# CPU_V1_1.net
KiCad netlist of a schematic drawn in EAGLE
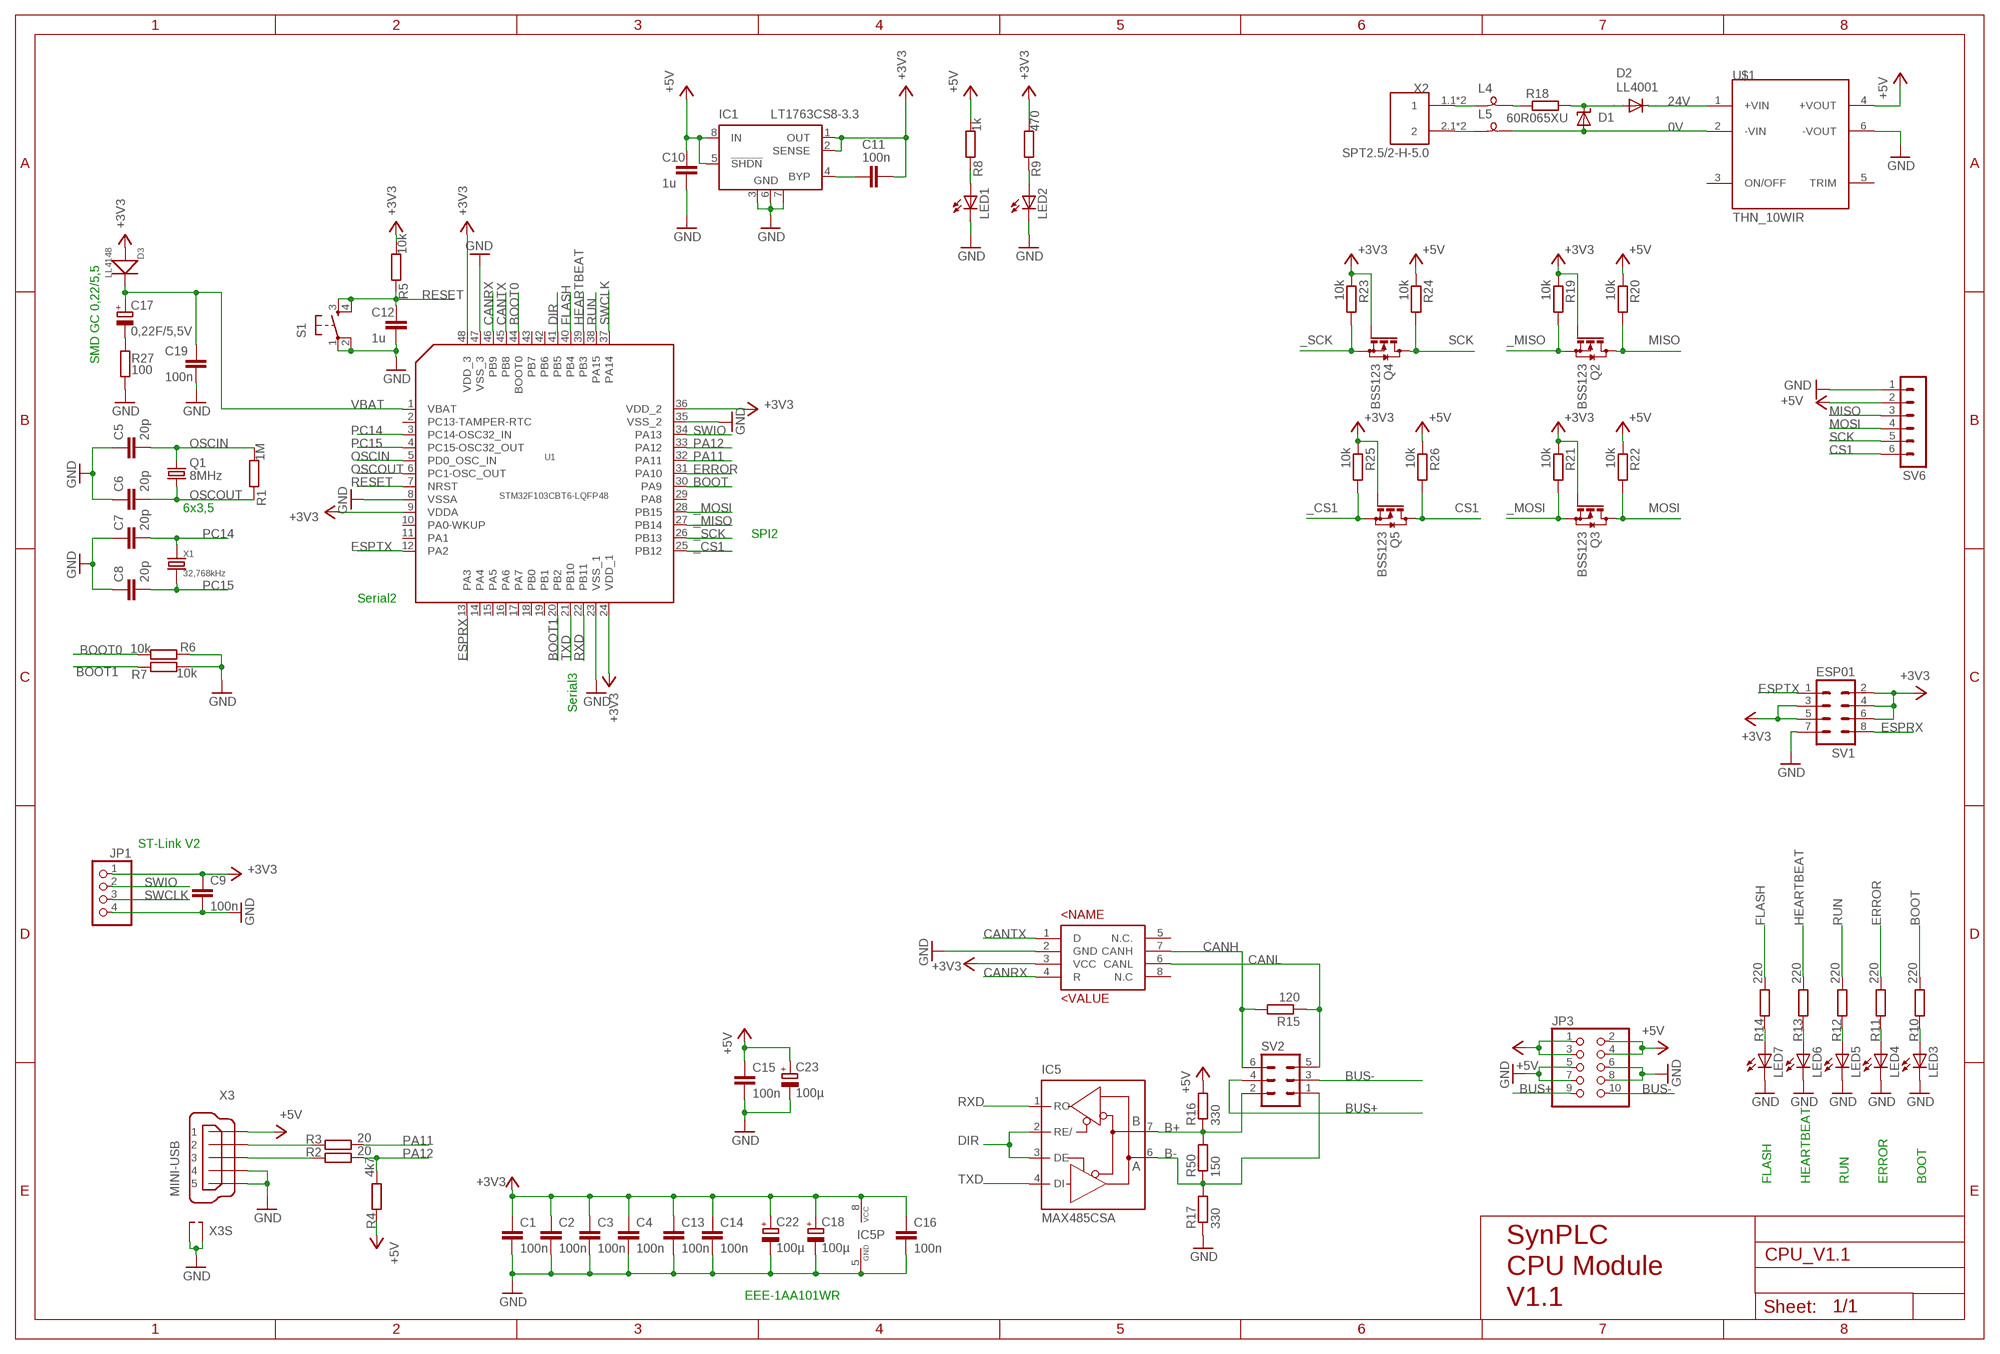
[diagram p0: schematic, sheet 1]

(export (version "E")
  (design (tool "Eeschema 10.0.6"))
  (components
    (comp (ref "C1")
      (value "100n")
      (footprint "eagle-import:C0805K")
      (libsource (lib "eagle-import") (part "C-EUC0805K"))
    )
    (comp (ref "C2")
      (value "100n")
      (footprint "eagle-import:C0805K")
      (libsource (lib "eagle-import") (part "C-EUC0805K"))
    )
    (comp (ref "C3")
      (value "100n")
      (footprint "eagle-import:C0805K")
      (libsource (lib "eagle-import") (part "C-EUC0805K"))
    )
    (comp (ref "C4")
      (value "100n")
      (footprint "eagle-import:C0805K")
      (libsource (lib "eagle-import") (part "C-EUC0805K"))
    )
    (comp (ref "C5")
      (value "20p")
      (footprint "eagle-import:C0805K")
      (libsource (lib "eagle-import") (part "C-EUC0805K"))
    )
    (comp (ref "C6")
      (value "20p")
      (footprint "eagle-import:C0805K")
      (libsource (lib "eagle-import") (part "C-EUC0805K"))
    )
    (comp (ref "C7")
      (value "20p")
      (footprint "eagle-import:C0805K")
      (libsource (lib "eagle-import") (part "C-EUC0805K"))
    )
    (comp (ref "C8")
      (value "20p")
      (footprint "eagle-import:C0805K")
      (libsource (lib "eagle-import") (part "C-EUC0805K"))
    )
    (comp (ref "C9")
      (value "100n")
      (footprint "eagle-import:C0805K")
      (libsource (lib "eagle-import") (part "C-EUC0805K"))
    )
    (comp (ref "C10")
      (value "1u")
      (footprint "eagle-import:C0805K")
      (libsource (lib "eagle-import") (part "C-EUC0805K"))
    )
    (comp (ref "C11")
      (value "100n")
      (footprint "eagle-import:C0805K")
      (libsource (lib "eagle-import") (part "C-EUC0805K"))
    )
    (comp (ref "C12")
      (value "1u")
      (footprint "eagle-import:C0805K")
      (libsource (lib "eagle-import") (part "C-EUC0805K"))
    )
    (comp (ref "C13")
      (value "100n")
      (footprint "eagle-import:C0805K")
      (libsource (lib "eagle-import") (part "C-EUC0805K"))
    )
    (comp (ref "C14")
      (value "100n")
      (footprint "eagle-import:C0805K")
      (libsource (lib "eagle-import") (part "C-EUC0805K"))
    )
    (comp (ref "C15")
      (value "100n")
      (footprint "eagle-import:C0805")
      (libsource (lib "eagle-import") (part "C-EUC0805"))
    )
    (comp (ref "C16")
      (value "100n")
      (footprint "eagle-import:C0805")
      (libsource (lib "eagle-import") (part "C-EUC0805"))
    )
    (comp (ref "C17")
      (value "0,22F/5,5V")
      (footprint "eagle-import:PANASONIC_G")
      (libsource (lib "eagle-import") (part "CPOL-EUG"))
    )
    (comp (ref "C18")
      (value "100µ")
      (footprint "eagle-import:153CLV-0505")
      (libsource (lib "eagle-import") (part "CPOL-EU153CLV-0505"))
    )
    (comp (ref "C19")
      (value "100n")
      (footprint "eagle-import:C0805K")
      (libsource (lib "eagle-import") (part "C-EUC0805K"))
    )
    (comp (ref "C22")
      (value "100µ")
      (footprint "eagle-import:153CLV-0505")
      (libsource (lib "eagle-import") (part "CPOL-EU153CLV-0505"))
    )
    (comp (ref "C23")
      (value "100µ")
      (footprint "eagle-import:153CLV-0505")
      (libsource (lib "eagle-import") (part "CPOL-EU153CLV-0505"))
    )
    (comp (ref "D1")
      (value "SUPPRESSOR-SMBJ")
      (footprint "eagle-import:SMBJ")
      (libsource (lib "eagle-import") (part "SUPPRESSOR-SMBJ"))
    )
    (comp (ref "D2")
      (value "LL4001")
      (footprint "eagle-import:SOD-123_MINI-SMA")
      (libsource (lib "eagle-import") (part "CGRM400-G1"))
    )
    (comp (ref "D3")
      (value "LL4148")
      (footprint "eagle-import:LL-34")
      (libsource (lib "eagle-import") (part "DIODE'1N4148-SMD'"))
    )
    (comp (ref "IC1")
      (value "LT1763CS8-3.3")
      (footprint "eagle-import:SOIC8")
      (libsource (lib "eagle-import") (part "LT1763CS8-3.3"))
    )
    (comp (ref "IC5")
      (value "MAX485CSA")
      (footprint "eagle-import:SO08")
      (fields (field (name "MF") "MAXIM") (field (name "MPN") "MAX481CSA"))
      (libsource (lib "eagle-import") (part "MAX481CSA"))
    )
    (comp (ref "JP1")
      (value "PINHD-1X4/90")
      (footprint "eagle-import:1X04_90")
      (libsource (lib "eagle-import") (part "PINHD-1X4/90"))
    )
    (comp (ref "JP3")
      (value "PINHD-2X5/90")
      (footprint "eagle-import:2X05_90")
      (libsource (lib "eagle-import") (part "PINHD-2X5/90"))
    )
    (comp (ref "L4")
      (value "SM-B5")
      (footprint "eagle-import:SM-B5")
      (libsource (lib "eagle-import") (part "SM-B5"))
    )
    (comp (ref "L5")
      (value "SM-B5")
      (footprint "eagle-import:SM-B5")
      (libsource (lib "eagle-import") (part "SM-B5"))
    )
    (comp (ref "LED1")
      (value "LEDSML0805")
      (footprint "eagle-import:SML0805")
      (libsource (lib "eagle-import") (part "LEDSML0805"))
    )
    (comp (ref "LED2")
      (value "LEDSML0805")
      (footprint "eagle-import:SML0805")
      (libsource (lib "eagle-import") (part "LEDSML0805"))
    )
    (comp (ref "LED3")
      (value "LED3MM")
      (footprint "eagle-import:LED3MM")
      (libsource (lib "eagle-import") (part "LED3MM"))
    )
    (comp (ref "LED4")
      (value "LED3MM")
      (footprint "eagle-import:LED3MM")
      (libsource (lib "eagle-import") (part "LED3MM"))
    )
    (comp (ref "LED5")
      (value "LED3MM")
      (footprint "eagle-import:LED3MM")
      (libsource (lib "eagle-import") (part "LED3MM"))
    )
    (comp (ref "LED6")
      (value "LED3MM")
      (footprint "eagle-import:LED3MM")
      (libsource (lib "eagle-import") (part "LED3MM"))
    )
    (comp (ref "LED7")
      (value "LED3MM")
      (footprint "eagle-import:LED3MM")
      (libsource (lib "eagle-import") (part "LED3MM"))
    )
    (comp (ref "Q1")
      (value "8MHz")
      (footprint "eagle-import:11.4X4.5")
      (libsource (lib "eagle-import") (part "KX-K"))
    )
    (comp (ref "Q2")
      (value "BSS123")
      (footprint "eagle-import:SOT23")
      (libsource (lib "eagle-import") (part "BSS123"))
    )
    (comp (ref "Q3")
      (value "BSS123")
      (footprint "eagle-import:SOT23")
      (libsource (lib "eagle-import") (part "BSS123"))
    )
    (comp (ref "Q4")
      (value "BSS123")
      (footprint "eagle-import:SOT23")
      (libsource (lib "eagle-import") (part "BSS123"))
    )
    (comp (ref "Q5")
      (value "BSS123")
      (footprint "eagle-import:SOT23")
      (libsource (lib "eagle-import") (part "BSS123"))
    )
    (comp (ref "R1")
      (value "1M")
      (footprint "eagle-import:R0805")
      (libsource (lib "eagle-import") (part "R-EU_R0805"))
    )
    (comp (ref "R2")
      (value "20")
      (footprint "eagle-import:R0805")
      (libsource (lib "eagle-import") (part "R-EU_R0805"))
    )
    (comp (ref "R3")
      (value "20")
      (footprint "eagle-import:R0805")
      (libsource (lib "eagle-import") (part "R-EU_R0805"))
    )
    (comp (ref "R4")
      (value "4k7")
      (footprint "eagle-import:R0805")
      (libsource (lib "eagle-import") (part "R-EU_R0805"))
    )
    (comp (ref "R5")
      (value "10k")
      (footprint "eagle-import:R0805")
      (libsource (lib "eagle-import") (part "R-EU_R0805"))
    )
    (comp (ref "R6")
      (value "10k")
      (footprint "eagle-import:R0805")
      (libsource (lib "eagle-import") (part "R-EU_R0805"))
    )
    (comp (ref "R7")
      (value "10k")
      (footprint "eagle-import:R0805")
      (libsource (lib "eagle-import") (part "R-EU_R0805"))
    )
    (comp (ref "R8")
      (value "1k")
      (footprint "eagle-import:R0805")
      (libsource (lib "eagle-import") (part "R-EU_R0805"))
    )
    (comp (ref "R9")
      (value "470")
      (footprint "eagle-import:R0805")
      (libsource (lib "eagle-import") (part "R-EU_R0805"))
    )
    (comp (ref "R10")
      (value "220")
      (footprint "eagle-import:R0805")
      (libsource (lib "eagle-import") (part "R-EU_R0805"))
    )
    (comp (ref "R11")
      (value "220")
      (footprint "eagle-import:R0805")
      (libsource (lib "eagle-import") (part "R-EU_R0805"))
    )
    (comp (ref "R12")
      (value "220")
      (footprint "eagle-import:R0805")
      (libsource (lib "eagle-import") (part "R-EU_R0805"))
    )
    (comp (ref "R13")
      (value "220")
      (footprint "eagle-import:R0805")
      (libsource (lib "eagle-import") (part "R-EU_R0805"))
    )
    (comp (ref "R14")
      (value "220")
      (footprint "eagle-import:R0805")
      (libsource (lib "eagle-import") (part "R-EU_R0805"))
    )
    (comp (ref "R15")
      (value "120")
      (footprint "eagle-import:R0805")
      (libsource (lib "eagle-import") (part "R-EU_R0805"))
    )
    (comp (ref "R16")
      (value "330")
      (footprint "eagle-import:R0805")
      (libsource (lib "eagle-import") (part "R-EU_R0805"))
    )
    (comp (ref "R17")
      (value "330")
      (footprint "eagle-import:R0805")
      (libsource (lib "eagle-import") (part "R-EU_R0805"))
    )
    (comp (ref "R18")
      (value "60R065XU")
      (footprint "eagle-import:0204_5")
      (libsource (lib "eagle-import") (part "R-EU_0204/5"))
    )
    (comp (ref "R19")
      (value "10k")
      (footprint "eagle-import:R0805")
      (libsource (lib "eagle-import") (part "R-EU_R0805"))
    )
    (comp (ref "R20")
      (value "10k")
      (footprint "eagle-import:R0805")
      (libsource (lib "eagle-import") (part "R-EU_R0805"))
    )
    (comp (ref "R21")
      (value "10k")
      (footprint "eagle-import:R0805")
      (libsource (lib "eagle-import") (part "R-EU_R0805"))
    )
    (comp (ref "R22")
      (value "10k")
      (footprint "eagle-import:R0805")
      (libsource (lib "eagle-import") (part "R-EU_R0805"))
    )
    (comp (ref "R23")
      (value "10k")
      (footprint "eagle-import:R0805")
      (libsource (lib "eagle-import") (part "R-EU_R0805"))
    )
    (comp (ref "R24")
      (value "10k")
      (footprint "eagle-import:R0805")
      (libsource (lib "eagle-import") (part "R-EU_R0805"))
    )
    (comp (ref "R25")
      (value "10k")
      (footprint "eagle-import:R0805")
      (libsource (lib "eagle-import") (part "R-EU_R0805"))
    )
    (comp (ref "R26")
      (value "10k")
      (footprint "eagle-import:R0805")
      (libsource (lib "eagle-import") (part "R-EU_R0805"))
    )
    (comp (ref "R27")
      (value "100")
      (footprint "eagle-import:R0805")
      (libsource (lib "eagle-import") (part "R-EU_R0805"))
    )
    (comp (ref "R50")
      (value "150")
      (footprint "eagle-import:R0805")
      (libsource (lib "eagle-import") (part "R-EU_R0805"))
    )
    (comp (ref "S1")
      (value "TAC_SWITCHPTH")
      (footprint "eagle-import:TACTILE-PTH")
      (libsource (lib "eagle-import") (part "TAC_SWITCHPTH"))
    )
    (comp (ref "SV1")
      (value "ESP01")
      (footprint "eagle-import:MA04-2")
      (libsource (lib "eagle-import") (part "MA04-2"))
    )
    (comp (ref "SV2")
      (value "MA03-2")
      (footprint "eagle-import:MA03-2")
      (libsource (lib "eagle-import") (part "MA03-2"))
    )
    (comp (ref "SV6")
      (value "MA06-1")
      (footprint "eagle-import:MA06-1")
      (libsource (lib "eagle-import") (part "MA06-1"))
    )
    (comp (ref "U$1")
      (value "THN_10WIR")
      (footprint "eagle-import:THN10WIR")
      (libsource (lib "eagle-import") (part "THN_10WIR"))
    )
    (comp (ref "U$3")
      (value "SN65HVD232")
      (footprint "eagle-import:SO-08")
      (libsource (lib "eagle-import") (part "SN65HVD232"))
    )
    (comp (ref "U1")
      (value "STM32F103CBT6-LQFP48")
      (footprint "eagle-import:LQFP48-0.5-7X7MM")
      (fields (field (name "MPN") "STM32F103CBT6"))
      (libsource (lib "eagle-import") (part "MCU-STM32F103CBT6(LQFP48)"))
    )
    (comp (ref "X1")
      (value "32,768kHz")
      (footprint "eagle-import:X2-2.0-D9.1XL3.3MM")
      (libsource (lib "eagle-import") (part "CRYSTAL'9133'"))
    )
    (comp (ref "X2")
      (value "SPT2.5/2-H-5.0")
      (footprint "eagle-import:SPT2")
      (libsource (lib "eagle-import") (part "SPT2.5/2-H-5.0"))
    )
    (comp (ref "X3")
      (value "MINI-USB")
      (footprint "eagle-import:32005-601")
      (libsource (lib "eagle-import") (part "MINI-USB_SHIELD5P2-32005-601"))
    )
  )
  (nets
    (net (code "1") (name "+3V3") (class "Default")
      (node (ref "C1") (pin "1") (pinfunction "1_1") (pintype "passive"))
      (node (ref "C11") (pin "1") (pinfunction "1_1") (pintype "passive"))
      (node (ref "C13") (pin "1") (pinfunction "1_1") (pintype "passive"))
      (node (ref "C14") (pin "1") (pinfunction "1_1") (pintype "passive"))
      (node (ref "C16") (pin "1") (pinfunction "1_1") (pintype "passive"))
      (node (ref "C18") (pin "+") (pinfunction "+_+") (pintype "passive"))
      (node (ref "C2") (pin "1") (pinfunction "1_1") (pintype "passive"))
      (node (ref "C22") (pin "+") (pinfunction "+_+") (pintype "passive"))
      (node (ref "C3") (pin "1") (pinfunction "1_1") (pintype "passive"))
      (node (ref "C4") (pin "1") (pinfunction "1_1") (pintype "passive"))
      (node (ref "C9") (pin "1") (pinfunction "1_1") (pintype "passive"))
      (node (ref "D3") (pin "A") (pinfunction "+_A") (pintype "passive"))
      (node (ref "IC1") (pin "1") (pinfunction "OUT_1") (pintype "passive"))
      (node (ref "IC1") (pin "2") (pinfunction "SENSE_2") (pintype "input"))
      (node (ref "IC5") (pin "8") (pinfunction "VCC_8") (pintype "power_in"))
      (node (ref "JP1") (pin "1") (pinfunction "1_1") (pintype "passive"))
      (node (ref "Q2") (pin "1") (pinfunction "G_1") (pintype "passive"))
      (node (ref "Q3") (pin "1") (pinfunction "G_1") (pintype "passive"))
      (node (ref "Q4") (pin "1") (pinfunction "G_1") (pintype "passive"))
      (node (ref "Q5") (pin "1") (pinfunction "G_1") (pintype "passive"))
      (node (ref "R19") (pin "1") (pinfunction "1_1") (pintype "passive"))
      (node (ref "R21") (pin "1") (pinfunction "1_1") (pintype "passive"))
      (node (ref "R23") (pin "1") (pinfunction "1_1") (pintype "passive"))
      (node (ref "R25") (pin "1") (pinfunction "1_1") (pintype "passive"))
      (node (ref "R5") (pin "2") (pinfunction "2_2") (pintype "passive"))
      (node (ref "R9") (pin "2") (pinfunction "2_2") (pintype "passive"))
      (node (ref "SV1") (pin "2") (pinfunction "2_2") (pintype "passive"))
      (node (ref "SV1") (pin "3") (pinfunction "3_3") (pintype "passive"))
      (node (ref "SV1") (pin "4") (pinfunction "4_4") (pintype "passive"))
      (node (ref "SV1") (pin "5") (pinfunction "5_5") (pintype "passive"))
      (node (ref "SV1") (pin "6") (pinfunction "6_6") (pintype "passive"))
      (node (ref "U$3") (pin "3") (pinfunction "VCC_3") (pintype "bidirectional"))
      (node (ref "U1") (pin "24") (pinfunction "VDD_1_24") (pintype "bidirectional"))
      (node (ref "U1") (pin "36") (pinfunction "VDD_2_36") (pintype "bidirectional"))
      (node (ref "U1") (pin "48") (pinfunction "VDD_3_48") (pintype "bidirectional"))
      (node (ref "U1") (pin "9") (pinfunction "VDDA_9") (pintype "bidirectional"))
    )
    (net (code "2") (name "+5V") (class "Default")
      (node (ref "C10") (pin "1") (pinfunction "1_1") (pintype "passive"))
      (node (ref "C15") (pin "1") (pinfunction "1_1") (pintype "passive"))
      (node (ref "C23") (pin "+") (pinfunction "+_+") (pintype "passive"))
      (node (ref "IC1") (pin "5") (pinfunction "~{SHDN}_5") (pintype "input"))
      (node (ref "IC1") (pin "8") (pinfunction "IN_8") (pintype "input"))
      (node (ref "JP3") (pin "1") (pinfunction "1_1") (pintype "passive"))
      (node (ref "JP3") (pin "2") (pinfunction "2_2") (pintype "passive"))
      (node (ref "JP3") (pin "3") (pinfunction "3_3") (pintype "passive"))
      (node (ref "JP3") (pin "4") (pinfunction "4_4") (pintype "passive"))
      (node (ref "R16") (pin "2") (pinfunction "2_2") (pintype "passive"))
      (node (ref "R20") (pin "1") (pinfunction "1_1") (pintype "passive"))
      (node (ref "R22") (pin "1") (pinfunction "1_1") (pintype "passive"))
      (node (ref "R24") (pin "1") (pinfunction "1_1") (pintype "passive"))
      (node (ref "R26") (pin "1") (pinfunction "1_1") (pintype "passive"))
      (node (ref "R4") (pin "1") (pinfunction "1_1") (pintype "passive"))
      (node (ref "R8") (pin "2") (pinfunction "2_2") (pintype "passive"))
      (node (ref "SV6") (pin "2") (pinfunction "2_2") (pintype "passive"))
      (node (ref "U$1") (pin "4") (pinfunction "+VOUT_4") (pintype "bidirectional"))
      (node (ref "X3") (pin "1") (pinfunction "1_1") (pintype "passive"))
    )
    (net (code "3") (name "/0V") (class "Default")
      (node (ref "D1") (pin "A") (pinfunction "A_A") (pintype "passive"))
      (node (ref "L5") (pin "1") (pinfunction "1_1") (pintype "passive"))
      (node (ref "U$1") (pin "2") (pinfunction "-VIN_2") (pintype "bidirectional"))
    )
    (net (code "4") (name "/24V") (class "Default")
      (node (ref "D2") (pin "C") (pinfunction "C_C") (pintype "passive"))
      (node (ref "U$1") (pin "1") (pinfunction "+VIN_1") (pintype "bidirectional"))
    )
    (net (code "5") (name "/B+") (class "Default")
      (node (ref "IC5") (pin "7") (pinfunction "B_7") (pintype "passive"))
      (node (ref "R16") (pin "1") (pinfunction "1_1") (pintype "passive"))
      (node (ref "R50") (pin "2") (pinfunction "2_2") (pintype "passive"))
      (node (ref "SV2") (pin "2") (pinfunction "2_2") (pintype "passive"))
    )
    (net (code "6") (name "/B-") (class "Default")
      (node (ref "IC5") (pin "6") (pinfunction "A_6") (pintype "passive"))
      (node (ref "R17") (pin "2") (pinfunction "2_2") (pintype "passive"))
      (node (ref "R50") (pin "1") (pinfunction "1_1") (pintype "passive"))
      (node (ref "SV2") (pin "1") (pinfunction "1_1") (pintype "passive"))
    )
    (net (code "7") (name "/BOOT") (class "Default")
      (node (ref "R10") (pin "2") (pinfunction "2_2") (pintype "passive"))
      (node (ref "U1") (pin "30") (pinfunction "PA9_30") (pintype "bidirectional"))
    )
    (net (code "8") (name "/BOOT0") (class "Default")
      (node (ref "R6") (pin "2") (pinfunction "2_2") (pintype "passive"))
      (node (ref "U1") (pin "44") (pinfunction "BOOT0_44") (pintype "bidirectional"))
    )
    (net (code "9") (name "/BOOT1") (class "Default")
      (node (ref "R7") (pin "1") (pinfunction "1_1") (pintype "passive"))
      (node (ref "U1") (pin "20") (pinfunction "PB2_20") (pintype "bidirectional"))
    )
    (net (code "10") (name "/BUS+") (class "Default")
      (node (ref "JP3") (pin "9") (pinfunction "9_9") (pintype "passive"))
      (node (ref "SV2") (pin "4") (pinfunction "4_4") (pintype "passive"))
    )
    (net (code "11") (name "/BUS-") (class "Default")
      (node (ref "JP3") (pin "10") (pinfunction "10_10") (pintype "passive"))
      (node (ref "SV2") (pin "3") (pinfunction "3_3") (pintype "passive"))
    )
    (net (code "12") (name "/CANH") (class "Default")
      (node (ref "R15") (pin "2") (pinfunction "2_2") (pintype "passive"))
      (node (ref "SV2") (pin "6") (pinfunction "6_6") (pintype "passive"))
      (node (ref "U$3") (pin "7") (pinfunction "CANH_7") (pintype "bidirectional"))
    )
    (net (code "13") (name "/CANL") (class "Default")
      (node (ref "R15") (pin "1") (pinfunction "1_1") (pintype "passive"))
      (node (ref "SV2") (pin "5") (pinfunction "5_5") (pintype "passive"))
      (node (ref "U$3") (pin "6") (pinfunction "CANL_6") (pintype "bidirectional"))
    )
    (net (code "14") (name "/CANRX") (class "Default")
      (node (ref "U$3") (pin "4") (pinfunction "R_4") (pintype "bidirectional"))
      (node (ref "U1") (pin "46") (pinfunction "PB9_46") (pintype "bidirectional"))
    )
    (net (code "15") (name "/CANTX") (class "Default")
      (node (ref "U$3") (pin "1") (pinfunction "D_1") (pintype "bidirectional"))
      (node (ref "U1") (pin "45") (pinfunction "PB8_45") (pintype "bidirectional"))
    )
    (net (code "16") (name "/CS1") (class "Default")
      (node (ref "Q5") (pin "3") (pinfunction "D_3") (pintype "passive"))
      (node (ref "R26") (pin "2") (pinfunction "2_2") (pintype "passive"))
      (node (ref "SV6") (pin "6") (pinfunction "6_6") (pintype "passive"))
    )
    (net (code "17") (name "/DIR") (class "Default")
      (node (ref "IC5") (pin "2") (pinfunction "RE/_2") (pintype "input"))
      (node (ref "IC5") (pin "3") (pinfunction "DE_3") (pintype "input"))
      (node (ref "U1") (pin "41") (pinfunction "PB5_41") (pintype "bidirectional"))
    )
    (net (code "18") (name "/ERROR") (class "Default")
      (node (ref "R11") (pin "2") (pinfunction "2_2") (pintype "passive"))
      (node (ref "U1") (pin "31") (pinfunction "PA10_31") (pintype "bidirectional"))
    )
    (net (code "19") (name "/ESPRX") (class "Default")
      (node (ref "SV1") (pin "8") (pinfunction "8_8") (pintype "passive"))
      (node (ref "U1") (pin "13") (pinfunction "PA3_13") (pintype "bidirectional"))
    )
    (net (code "20") (name "/ESPTX") (class "Default")
      (node (ref "SV1") (pin "1") (pinfunction "1_1") (pintype "passive"))
      (node (ref "U1") (pin "12") (pinfunction "PA2_12") (pintype "bidirectional"))
    )
    (net (code "21") (name "/FLASH") (class "Default")
      (node (ref "R14") (pin "2") (pinfunction "2_2") (pintype "passive"))
      (node (ref "U1") (pin "40") (pinfunction "PB4_40") (pintype "bidirectional"))
    )
    (net (code "22") (name "/HEARTBEAT") (class "Default")
      (node (ref "R13") (pin "2") (pinfunction "2_2") (pintype "passive"))
      (node (ref "U1") (pin "39") (pinfunction "PB3_39") (pintype "bidirectional"))
    )
    (net (code "23") (name "/MISO") (class "Default")
      (node (ref "Q2") (pin "3") (pinfunction "D_3") (pintype "passive"))
      (node (ref "R20") (pin "2") (pinfunction "2_2") (pintype "passive"))
      (node (ref "SV6") (pin "3") (pinfunction "3_3") (pintype "passive"))
    )
    (net (code "24") (name "/MOSI") (class "Default")
      (node (ref "Q3") (pin "3") (pinfunction "D_3") (pintype "passive"))
      (node (ref "R22") (pin "2") (pinfunction "2_2") (pintype "passive"))
      (node (ref "SV6") (pin "4") (pinfunction "4_4") (pintype "passive"))
    )
    (net (code "25") (name "/OSCIN") (class "Default")
      (node (ref "C5") (pin "2") (pinfunction "2_2") (pintype "passive"))
      (node (ref "Q1") (pin "2") (pinfunction "2_2") (pintype "passive"))
      (node (ref "R1") (pin "2") (pinfunction "2_2") (pintype "passive"))
      (node (ref "U1") (pin "5") (pinfunction "PD0_OSC_IN_5") (pintype "bidirectional"))
    )
    (net (code "26") (name "/OSCOUT") (class "Default")
      (node (ref "C6") (pin "2") (pinfunction "2_2") (pintype "passive"))
      (node (ref "Q1") (pin "1") (pinfunction "1_1") (pintype "passive"))
      (node (ref "R1") (pin "1") (pinfunction "1_1") (pintype "passive"))
      (node (ref "U1") (pin "6") (pinfunction "PC1-OSC_OUT_6") (pintype "bidirectional"))
    )
    (net (code "27") (name "/PA11") (class "Default")
      (node (ref "R3") (pin "2") (pinfunction "2_2") (pintype "passive"))
      (node (ref "U1") (pin "32") (pinfunction "PA11_32") (pintype "bidirectional"))
    )
    (net (code "28") (name "/PA12") (class "Default")
      (node (ref "R2") (pin "2") (pinfunction "2_2") (pintype "passive"))
      (node (ref "R4") (pin "2") (pinfunction "2_2") (pintype "passive"))
      (node (ref "U1") (pin "33") (pinfunction "PA12_33") (pintype "bidirectional"))
    )
    (net (code "29") (name "/PC14") (class "Default")
      (node (ref "C7") (pin "2") (pinfunction "2_2") (pintype "passive"))
      (node (ref "U1") (pin "3") (pinfunction "PC14-OSC32_IN_3") (pintype "bidirectional"))
      (node (ref "X1") (pin "2") (pinfunction "2_2") (pintype "passive"))
    )
    (net (code "30") (name "/PC15") (class "Default")
      (node (ref "C8") (pin "2") (pinfunction "2_2") (pintype "passive"))
      (node (ref "U1") (pin "4") (pinfunction "PC15-OSC32_OUT_4") (pintype "bidirectional"))
      (node (ref "X1") (pin "1") (pinfunction "1_1") (pintype "passive"))
    )
    (net (code "31") (name "/RESET") (class "Default")
      (node (ref "C12") (pin "1") (pinfunction "1_1") (pintype "passive"))
      (node (ref "R5") (pin "1") (pinfunction "1_1") (pintype "passive"))
      (node (ref "S1") (pin "3") (pinfunction "3_3") (pintype "passive"))
      (node (ref "S1") (pin "4") (pinfunction "4_4") (pintype "passive"))
      (node (ref "U1") (pin "7") (pinfunction "NRST_7") (pintype "bidirectional"))
    )
    (net (code "32") (name "/RUN") (class "Default")
      (node (ref "R12") (pin "2") (pinfunction "2_2") (pintype "passive"))
      (node (ref "U1") (pin "38") (pinfunction "PA15_38") (pintype "bidirectional"))
    )
    (net (code "33") (name "/RXD") (class "Default")
      (node (ref "IC5") (pin "1") (pinfunction "RO_1") (pintype "output"))
      (node (ref "U1") (pin "22") (pinfunction "PB11_22") (pintype "bidirectional"))
    )
    (net (code "34") (name "/SCK") (class "Default")
      (node (ref "Q4") (pin "3") (pinfunction "D_3") (pintype "passive"))
      (node (ref "R24") (pin "2") (pinfunction "2_2") (pintype "passive"))
      (node (ref "SV6") (pin "5") (pinfunction "5_5") (pintype "passive"))
    )
    (net (code "35") (name "/SWCLK") (class "Default")
      (node (ref "JP1") (pin "3") (pinfunction "3_3") (pintype "passive"))
      (node (ref "U1") (pin "37") (pinfunction "PA14_37") (pintype "bidirectional"))
    )
    (net (code "36") (name "/SWIO") (class "Default")
      (node (ref "JP1") (pin "2") (pinfunction "2_2") (pintype "passive"))
      (node (ref "U1") (pin "34") (pinfunction "PA13_34") (pintype "bidirectional"))
    )
    (net (code "37") (name "/TXD") (class "Default")
      (node (ref "IC5") (pin "4") (pinfunction "DI_4") (pintype "input"))
      (node (ref "U1") (pin "21") (pinfunction "PB10_21") (pintype "bidirectional"))
    )
    (net (code "38") (name "/VBAT") (class "Default")
      (node (ref "C17") (pin "+") (pinfunction "+_+") (pintype "passive"))
      (node (ref "C19") (pin "1") (pinfunction "1_1") (pintype "passive"))
      (node (ref "D3") (pin "C") (pinfunction "-_C") (pintype "passive"))
      (node (ref "U1") (pin "1") (pinfunction "VBAT_1") (pintype "bidirectional"))
    )
    (net (code "39") (name "/_CS1") (class "Default")
      (node (ref "Q5") (pin "2") (pinfunction "S_2") (pintype "passive"))
      (node (ref "R25") (pin "2") (pinfunction "2_2") (pintype "passive"))
      (node (ref "U1") (pin "25") (pinfunction "PB12_25") (pintype "bidirectional"))
    )
    (net (code "40") (name "/_MISO") (class "Default")
      (node (ref "Q2") (pin "2") (pinfunction "S_2") (pintype "passive"))
      (node (ref "R19") (pin "2") (pinfunction "2_2") (pintype "passive"))
      (node (ref "U1") (pin "27") (pinfunction "PB14_27") (pintype "bidirectional"))
    )
    (net (code "41") (name "/_MOSI") (class "Default")
      (node (ref "Q3") (pin "2") (pinfunction "S_2") (pintype "passive"))
      (node (ref "R21") (pin "2") (pinfunction "2_2") (pintype "passive"))
      (node (ref "U1") (pin "28") (pinfunction "PB15_28") (pintype "bidirectional"))
    )
    (net (code "42") (name "/_SCK") (class "Default")
      (node (ref "Q4") (pin "2") (pinfunction "S_2") (pintype "passive"))
      (node (ref "R23") (pin "2") (pinfunction "2_2") (pintype "passive"))
      (node (ref "U1") (pin "26") (pinfunction "PB13_26") (pintype "bidirectional"))
    )
    (net (code "43") (name "GND") (class "Default")
      (node (ref "C1") (pin "2") (pinfunction "2_2") (pintype "passive"))
      (node (ref "C10") (pin "2") (pinfunction "2_2") (pintype "passive"))
      (node (ref "C12") (pin "2") (pinfunction "2_2") (pintype "passive"))
      (node (ref "C13") (pin "2") (pinfunction "2_2") (pintype "passive"))
      (node (ref "C14") (pin "2") (pinfunction "2_2") (pintype "passive"))
      (node (ref "C15") (pin "2") (pinfunction "2_2") (pintype "passive"))
      (node (ref "C16") (pin "2") (pinfunction "2_2") (pintype "passive"))
      (node (ref "C18") (pin "-") (pinfunction "-_-") (pintype "passive"))
      (node (ref "C19") (pin "2") (pinfunction "2_2") (pintype "passive"))
      (node (ref "C2") (pin "2") (pinfunction "2_2") (pintype "passive"))
      (node (ref "C22") (pin "-") (pinfunction "-_-") (pintype "passive"))
      (node (ref "C23") (pin "-") (pinfunction "-_-") (pintype "passive"))
      (node (ref "C3") (pin "2") (pinfunction "2_2") (pintype "passive"))
      (node (ref "C4") (pin "2") (pinfunction "2_2") (pintype "passive"))
      (node (ref "C5") (pin "1") (pinfunction "1_1") (pintype "passive"))
      (node (ref "C6") (pin "1") (pinfunction "1_1") (pintype "passive"))
      (node (ref "C7") (pin "1") (pinfunction "1_1") (pintype "passive"))
      (node (ref "C8") (pin "1") (pinfunction "1_1") (pintype "passive"))
      (node (ref "C9") (pin "2") (pinfunction "2_2") (pintype "passive"))
      (node (ref "IC1") (pin "3") (pinfunction "GND_3") (pintype "power_in"))
      (node (ref "IC1") (pin "6") (pinfunction "GND_6") (pintype "power_in"))
      (node (ref "IC1") (pin "7") (pinfunction "GND_7") (pintype "power_in"))
      (node (ref "IC5") (pin "5") (pinfunction "GND_5") (pintype "power_in"))
      (node (ref "JP1") (pin "4") (pinfunction "4_4") (pintype "passive"))
      (node (ref "JP3") (pin "5") (pinfunction "5_5") (pintype "passive"))
      (node (ref "JP3") (pin "6") (pinfunction "6_6") (pintype "passive"))
      (node (ref "JP3") (pin "7") (pinfunction "7_7") (pintype "passive"))
      (node (ref "JP3") (pin "8") (pinfunction "8_8") (pintype "passive"))
      (node (ref "LED1") (pin "C") (pinfunction "C_C") (pintype "passive"))
      (node (ref "LED2") (pin "C") (pinfunction "C_C") (pintype "passive"))
      (node (ref "LED3") (pin "K") (pinfunction "C_K") (pintype "passive"))
      (node (ref "LED4") (pin "K") (pinfunction "C_K") (pintype "passive"))
      (node (ref "LED5") (pin "K") (pinfunction "C_K") (pintype "passive"))
      (node (ref "LED6") (pin "K") (pinfunction "C_K") (pintype "passive"))
      (node (ref "LED7") (pin "K") (pinfunction "C_K") (pintype "passive"))
      (node (ref "R17") (pin "1") (pinfunction "1_1") (pintype "passive"))
      (node (ref "R27") (pin "1") (pinfunction "1_1") (pintype "passive"))
      (node (ref "R6") (pin "1") (pinfunction "1_1") (pintype "passive"))
      (node (ref "R7") (pin "2") (pinfunction "2_2") (pintype "passive"))
      (node (ref "S1") (pin "1") (pinfunction "1_1") (pintype "passive"))
      (node (ref "S1") (pin "2") (pinfunction "2_2") (pintype "passive"))
      (node (ref "SV1") (pin "7") (pinfunction "7_7") (pintype "passive"))
      (node (ref "SV6") (pin "1") (pinfunction "1_1") (pintype "passive"))
      (node (ref "U$1") (pin "6") (pinfunction "-VOUT_6") (pintype "bidirectional"))
      (node (ref "U$3") (pin "2") (pinfunction "GND_2") (pintype "bidirectional"))
      (node (ref "U1") (pin "23") (pinfunction "VSS_1_23") (pintype "bidirectional"))
      (node (ref "U1") (pin "35") (pinfunction "VSS_2_35") (pintype "bidirectional"))
      (node (ref "U1") (pin "47") (pinfunction "VSS_3_47") (pintype "bidirectional"))
      (node (ref "U1") (pin "8") (pinfunction "VSSA_8") (pintype "bidirectional"))
      (node (ref "X3") (pin "4") (pinfunction "4_4") (pintype "passive"))
      (node (ref "X3") (pin "5") (pinfunction "5_5") (pintype "passive"))
      (node (ref "X3") (pin "M1") (pinfunction "S1_M1") (pintype "passive"))
      (node (ref "X3") (pin "M2") (pinfunction "S2_M2") (pintype "passive"))
    )
    (net (code "44") (name "Net-(C17-Pad-)") (class "Default")
      (node (ref "C17") (pin "-") (pinfunction "-_-") (pintype "passive"))
      (node (ref "R27") (pin "2") (pinfunction "2_2") (pintype "passive"))
    )
    (net (code "45") (name "Net-(D1-PadC)") (class "Default")
      (node (ref "D1") (pin "C") (pinfunction "C_C") (pintype "passive"))
      (node (ref "D2") (pin "A") (pinfunction "A_A") (pintype "passive"))
      (node (ref "R18") (pin "2") (pinfunction "2_2") (pintype "passive"))
    )
    (net (code "46") (name "Net-(IC1-BYP)") (class "Default")
      (node (ref "C11") (pin "2") (pinfunction "2_2") (pintype "passive"))
      (node (ref "IC1") (pin "4") (pinfunction "BYP_4") (pintype "input"))
    )
    (net (code "47") (name "Net-(L4-Pad1)") (class "Default")
      (node (ref "L4") (pin "1") (pinfunction "1_1") (pintype "passive"))
      (node (ref "R18") (pin "1") (pinfunction "1_1") (pintype "passive"))
    )
    (net (code "48") (name "Net-(L4-Pad2)") (class "Default")
      (node (ref "L4") (pin "2") (pinfunction "2_2") (pintype "passive"))
      (node (ref "X2") (pin "1.1") (pinfunction "1_1.1") (pintype "bidirectional"))
      (node (ref "X2") (pin "1.2") (pinfunction "1_1.2") (pintype "bidirectional"))
    )
    (net (code "49") (name "Net-(L5-Pad2)") (class "Default")
      (node (ref "L5") (pin "2") (pinfunction "2_2") (pintype "passive"))
      (node (ref "X2") (pin "2.1") (pinfunction "2_2.1") (pintype "bidirectional"))
      (node (ref "X2") (pin "2.2") (pinfunction "2_2.2") (pintype "bidirectional"))
    )
    (net (code "50") (name "Net-(LED1-PadA)") (class "Default")
      (node (ref "LED1") (pin "A") (pinfunction "A_A") (pintype "passive"))
      (node (ref "R8") (pin "1") (pinfunction "1_1") (pintype "passive"))
    )
    (net (code "51") (name "Net-(LED2-PadA)") (class "Default")
      (node (ref "LED2") (pin "A") (pinfunction "A_A") (pintype "passive"))
      (node (ref "R9") (pin "1") (pinfunction "1_1") (pintype "passive"))
    )
    (net (code "52") (name "Net-(LED3-PadA)") (class "Default")
      (node (ref "LED3") (pin "A") (pinfunction "A_A") (pintype "passive"))
      (node (ref "R10") (pin "1") (pinfunction "1_1") (pintype "passive"))
    )
    (net (code "53") (name "Net-(LED4-PadA)") (class "Default")
      (node (ref "LED4") (pin "A") (pinfunction "A_A") (pintype "passive"))
      (node (ref "R11") (pin "1") (pinfunction "1_1") (pintype "passive"))
    )
    (net (code "54") (name "Net-(LED5-PadA)") (class "Default")
      (node (ref "LED5") (pin "A") (pinfunction "A_A") (pintype "passive"))
      (node (ref "R12") (pin "1") (pinfunction "1_1") (pintype "passive"))
    )
    (net (code "55") (name "Net-(LED6-PadA)") (class "Default")
      (node (ref "LED6") (pin "A") (pinfunction "A_A") (pintype "passive"))
      (node (ref "R13") (pin "1") (pinfunction "1_1") (pintype "passive"))
    )
    (net (code "56") (name "Net-(LED7-PadA)") (class "Default")
      (node (ref "LED7") (pin "A") (pinfunction "A_A") (pintype "passive"))
      (node (ref "R14") (pin "1") (pinfunction "1_1") (pintype "passive"))
    )
    (net (code "57") (name "Net-(R2-Pad1)") (class "Default")
      (node (ref "R2") (pin "1") (pinfunction "1_1") (pintype "passive"))
      (node (ref "X3") (pin "3") (pinfunction "3_3") (pintype "passive"))
    )
    (net (code "58") (name "Net-(R3-Pad1)") (class "Default")
      (node (ref "R3") (pin "1") (pinfunction "1_1") (pintype "passive"))
      (node (ref "X3") (pin "2") (pinfunction "2_2") (pintype "passive"))
    )
    (net (code "59") (name "unconnected-(U$1-ON{slash}OFF-Pad3)") (class "Default")
      (node (ref "U$1") (pin "3") (pinfunction "ON/OFF_3") (pintype "bidirectional"))
    )
    (net (code "60") (name "unconnected-(U$1-TRIM-Pad5)") (class "Default")
      (node (ref "U$1") (pin "5") (pinfunction "TRIM_5") (pintype "bidirectional"))
    )
    (net (code "61") (name "unconnected-(U$3-N.C-Pad8)") (class "Default")
      (node (ref "U$3") (pin "8") (pinfunction "N.C_8") (pintype "no_connect"))
    )
    (net (code "62") (name "unconnected-(U$3-N.C.-Pad5)") (class "Default")
      (node (ref "U$3") (pin "5") (pinfunction "N.C._5") (pintype "no_connect"))
    )
    (net (code "63") (name "unconnected-(U1-PA0-WKUP-Pad10)") (class "Default")
      (node (ref "U1") (pin "10") (pinfunction "PA0-WKUP_10") (pintype "bidirectional"))
    )
    (net (code "64") (name "unconnected-(U1-PA1-Pad11)") (class "Default")
      (node (ref "U1") (pin "11") (pinfunction "PA1_11") (pintype "bidirectional"))
    )
    (net (code "65") (name "unconnected-(U1-PA4-Pad14)") (class "Default")
      (node (ref "U1") (pin "14") (pinfunction "PA4_14") (pintype "bidirectional"))
    )
    (net (code "66") (name "unconnected-(U1-PA5-Pad15)") (class "Default")
      (node (ref "U1") (pin "15") (pinfunction "PA5_15") (pintype "bidirectional"))
    )
    (net (code "67") (name "unconnected-(U1-PA6-Pad16)") (class "Default")
      (node (ref "U1") (pin "16") (pinfunction "PA6_16") (pintype "bidirectional"))
    )
    (net (code "68") (name "unconnected-(U1-PA7-Pad17)") (class "Default")
      (node (ref "U1") (pin "17") (pinfunction "PA7_17") (pintype "bidirectional"))
    )
    (net (code "69") (name "unconnected-(U1-PA8-Pad29)") (class "Default")
      (node (ref "U1") (pin "29") (pinfunction "PA8_29") (pintype "bidirectional"))
    )
    (net (code "70") (name "unconnected-(U1-PB0-Pad18)") (class "Default")
      (node (ref "U1") (pin "18") (pinfunction "PB0_18") (pintype "bidirectional"))
    )
    (net (code "71") (name "unconnected-(U1-PB1-Pad19)") (class "Default")
      (node (ref "U1") (pin "19") (pinfunction "PB1_19") (pintype "bidirectional"))
    )
    (net (code "72") (name "unconnected-(U1-PB6-Pad42)") (class "Default")
      (node (ref "U1") (pin "42") (pinfunction "PB6_42") (pintype "bidirectional"))
    )
    (net (code "73") (name "unconnected-(U1-PB7-Pad43)") (class "Default")
      (node (ref "U1") (pin "43") (pinfunction "PB7_43") (pintype "bidirectional"))
    )
    (net (code "74") (name "unconnected-(U1-PC13-TAMPER-RTC-Pad2)") (class "Default")
      (node (ref "U1") (pin "2") (pinfunction "PC13-TAMPER-RTC_2") (pintype "bidirectional"))
    )
  )
)
